# dfp_grove.net
KiCad netlist of a schematic drawn in EAGLE
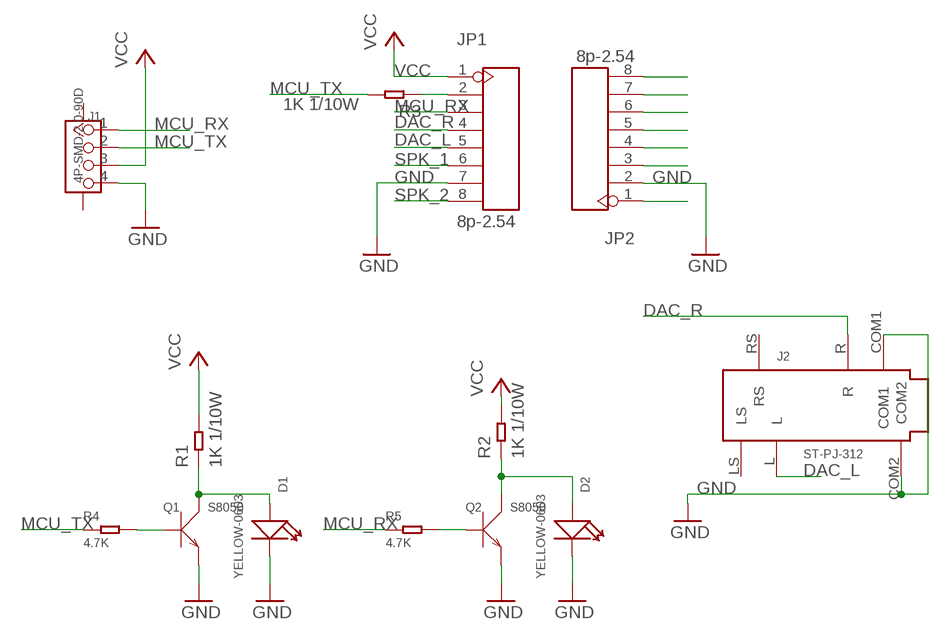
[diagram p0: schematic, sheet 1]

(export (version "E")
  (design (tool "Eeschema 10.0.6"))
  (components
    (comp (ref "D1")
      (value "YELLOW-0603")
      (footprint "eagle-import:LED-0603")
      (fields (field (name "MPN") "19-217-Y5C-AM1N1VY-3T"))
      (libsource (lib "eagle-import") (part "SMD-LED-CLEAR-YELLOW(0603)"))
    )
    (comp (ref "D2")
      (value "YELLOW-0603")
      (footprint "eagle-import:LED-0603")
      (fields (field (name "MPN") "19-217-Y5C-AM1N1VY-3T"))
      (libsource (lib "eagle-import") (part "SMD-LED-CLEAR-YELLOW(0603)"))
    )
    (comp (ref "J1")
      (value "4P-SMD-2.0-90D")
      (footprint "eagle-import:HW4-SMD-2.0-90D")
      (libsource (lib "eagle-import") (part "GROVE-CONNECTOR-SMD-90D(4+2P-2.0)"))
    )
    (comp (ref "J2")
      (value "ST-PJ-312")
      (footprint "eagle-import:AUDIO6P-SMD-3.5-14.0X6.4X5.0MM")
      (libsource (lib "eagle-import") (part "AUDIO-JACK-6P-SMD(ST-PJ-312)"))
    )
    (comp (ref "JP1")
      (value "8p-2.54")
      (footprint "eagle-import:H8-2.54")
      (fields (field (name "MPN") "F185-1108A1BSYC1"))
      (libsource (lib "eagle-import") (part "DIP-BLACK-FEMALE-HEADER-VERT(8P-2.54)"))
    )
    (comp (ref "JP2")
      (value "8p-2.54")
      (footprint "eagle-import:H8-2.54")
      (fields (field (name "MPN") "F185-1108A1BSYC1"))
      (libsource (lib "eagle-import") (part "DIP-BLACK-FEMALE-HEADER-VERT(8P-2.54)"))
    )
    (comp (ref "Q1")
      (value "S8050")
      (footprint "eagle-import:SOT-23")
      (libsource (lib "eagle-import") (part "SMD-TRANSISTORS-NPN-25V-500MW-S8050(SOT-23)"))
    )
    (comp (ref "Q2")
      (value "S8050")
      (footprint "eagle-import:SOT-23")
      (libsource (lib "eagle-import") (part "SMD-TRANSISTORS-NPN-25V-500MW-S8050(SOT-23)"))
    )
    (comp (ref "R1")
      (value "1K 1/10W")
      (footprint "eagle-import:R0603")
      (fields (field (name "MPN") "RC0603JR-071KL"))
      (libsource (lib "eagle-import") (part "SMD-RES-1K-5%-1/10W(0603)"))
    )
    (comp (ref "R2")
      (value "1K 1/10W")
      (footprint "eagle-import:R0603")
      (fields (field (name "MPN") "RC0603JR-071KL"))
      (libsource (lib "eagle-import") (part "SMD-RES-1K-5%-1/10W(0603)"))
    )
    (comp (ref "R3")
      (value "1K 1/10W")
      (footprint "eagle-import:R0603")
      (fields (field (name "MPN") "RC0603JR-071KL"))
      (libsource (lib "eagle-import") (part "SMD-RES-1K-5%-1/10W(0603)"))
    )
    (comp (ref "R4")
      (value "4.7K")
      (footprint "eagle-import:R0603")
      (fields (field (name "MPN") "RC0603JR-074K7L"))
      (libsource (lib "eagle-import") (part "SMD-RES-4.7K-5%-1/10W(0603)"))
    )
    (comp (ref "R5")
      (value "4.7K")
      (footprint "eagle-import:R0603")
      (fields (field (name "MPN") "RC0603JR-074K7L"))
      (libsource (lib "eagle-import") (part "SMD-RES-4.7K-5%-1/10W(0603)"))
    )
  )
  (nets
    (net (code "1") (name "/DAC_L") (class "Default")
      (node (ref "J2") (pin "L") (pinfunction "L_L") (pintype "bidirectional"))
      (node (ref "JP1") (pin "5") (pinfunction "5_5") (pintype "bidirectional"))
    )
    (net (code "2") (name "/DAC_R") (class "Default")
      (node (ref "J2") (pin "R") (pinfunction "R_R") (pintype "bidirectional"))
      (node (ref "JP1") (pin "4") (pinfunction "4_4") (pintype "bidirectional"))
    )
    (net (code "3") (name "/MCU_RX") (class "Default")
      (node (ref "J1") (pin "1") (pinfunction "1_1") (pintype "bidirectional"))
      (node (ref "JP1") (pin "3") (pinfunction "3_3") (pintype "bidirectional"))
      (node (ref "R5") (pin "1") (pinfunction "1_1") (pintype "passive"))
    )
    (net (code "4") (name "/MCU_TX") (class "Default")
      (node (ref "J1") (pin "2") (pinfunction "2_2") (pintype "bidirectional"))
      (node (ref "R3") (pin "2") (pinfunction "2_2") (pintype "passive"))
      (node (ref "R4") (pin "1") (pinfunction "1_1") (pintype "passive"))
    )
    (net (code "5") (name "/SPK_1") (class "Default")
      (node (ref "JP1") (pin "6") (pinfunction "6_6") (pintype "bidirectional"))
    )
    (net (code "6") (name "/SPK_2") (class "Default")
      (node (ref "JP1") (pin "8") (pinfunction "8_8") (pintype "bidirectional"))
    )
    (net (code "7") (name "GND") (class "Default")
      (node (ref "D1") (pin "-") (pinfunction "-_-") (pintype "passive"))
      (node (ref "D2") (pin "-") (pinfunction "-_-") (pintype "passive"))
      (node (ref "J1") (pin "4") (pinfunction "4_4") (pintype "bidirectional"))
      (node (ref "J2") (pin "COM1") (pinfunction "COM1_COM1") (pintype "bidirectional"))
      (node (ref "J2") (pin "COM2") (pinfunction "COM2_COM2") (pintype "bidirectional"))
      (node (ref "JP1") (pin "7") (pinfunction "7_7") (pintype "bidirectional"))
      (node (ref "JP2") (pin "2") (pinfunction "2_2") (pintype "bidirectional"))
      (node (ref "Q1") (pin "2") (pinfunction "E_2") (pintype "passive"))
      (node (ref "Q2") (pin "2") (pinfunction "E_2") (pintype "passive"))
    )
    (net (code "8") (name "Net-(JP1-Pad2)") (class "Default")
      (node (ref "JP1") (pin "2") (pinfunction "2_2") (pintype "bidirectional"))
      (node (ref "R3") (pin "1") (pinfunction "1_1") (pintype "passive"))
    )
    (net (code "9") (name "Net-(Q1-B)") (class "Default")
      (node (ref "Q1") (pin "1") (pinfunction "B_1") (pintype "passive"))
      (node (ref "R4") (pin "2") (pinfunction "2_2") (pintype "passive"))
    )
    (net (code "10") (name "Net-(Q1-C)") (class "Default")
      (node (ref "D1") (pin "+") (pinfunction "+_+") (pintype "passive"))
      (node (ref "Q1") (pin "3") (pinfunction "C_3") (pintype "passive"))
      (node (ref "R1") (pin "1") (pinfunction "1_1") (pintype "passive"))
    )
    (net (code "11") (name "Net-(Q2-B)") (class "Default")
      (node (ref "Q2") (pin "1") (pinfunction "B_1") (pintype "passive"))
      (node (ref "R5") (pin "2") (pinfunction "2_2") (pintype "passive"))
    )
    (net (code "12") (name "Net-(Q2-C)") (class "Default")
      (node (ref "D2") (pin "+") (pinfunction "+_+") (pintype "passive"))
      (node (ref "Q2") (pin "3") (pinfunction "C_3") (pintype "passive"))
      (node (ref "R2") (pin "1") (pinfunction "1_1") (pintype "passive"))
    )
    (net (code "13") (name "VCC") (class "Default")
      (node (ref "J1") (pin "3") (pinfunction "3_3") (pintype "bidirectional"))
      (node (ref "JP1") (pin "1") (pinfunction "1_1") (pintype "bidirectional"))
      (node (ref "R1") (pin "2") (pinfunction "2_2") (pintype "passive"))
      (node (ref "R2") (pin "2") (pinfunction "2_2") (pintype "passive"))
    )
    (net (code "14") (name "unconnected-(J1-PadSS1)") (class "Default")
      (node (ref "J1") (pin "SS1") (pinfunction "SS1_SS1") (pintype "bidirectional"))
    )
    (net (code "15") (name "unconnected-(J1-PadSS2)") (class "Default")
      (node (ref "J1") (pin "SS2") (pinfunction "SS2_SS2") (pintype "bidirectional"))
    )
    (net (code "16") (name "unconnected-(J2-PadLS)") (class "Default")
      (node (ref "J2") (pin "LS") (pinfunction "LS_LS") (pintype "bidirectional"))
    )
    (net (code "17") (name "unconnected-(J2-PadRS)") (class "Default")
      (node (ref "J2") (pin "RS") (pinfunction "RS_RS") (pintype "bidirectional"))
    )
    (net (code "18") (name "unconnected-(JP2-Pad1)") (class "Default")
      (node (ref "JP2") (pin "1") (pinfunction "1_1") (pintype "bidirectional"))
    )
    (net (code "19") (name "unconnected-(JP2-Pad3)") (class "Default")
      (node (ref "JP2") (pin "3") (pinfunction "3_3") (pintype "bidirectional"))
    )
    (net (code "20") (name "unconnected-(JP2-Pad4)") (class "Default")
      (node (ref "JP2") (pin "4") (pinfunction "4_4") (pintype "bidirectional"))
    )
    (net (code "21") (name "unconnected-(JP2-Pad5)") (class "Default")
      (node (ref "JP2") (pin "5") (pinfunction "5_5") (pintype "bidirectional"))
    )
    (net (code "22") (name "unconnected-(JP2-Pad6)") (class "Default")
      (node (ref "JP2") (pin "6") (pinfunction "6_6") (pintype "bidirectional"))
    )
    (net (code "23") (name "unconnected-(JP2-Pad7)") (class "Default")
      (node (ref "JP2") (pin "7") (pinfunction "7_7") (pintype "bidirectional"))
    )
    (net (code "24") (name "unconnected-(JP2-Pad8)") (class "Default")
      (node (ref "JP2") (pin "8") (pinfunction "8_8") (pintype "bidirectional"))
    )
  )
)
